# lamloei_node32s3mini_cp2102_main_2layers.net
KiCad netlist of a schematic drawn in EAGLE
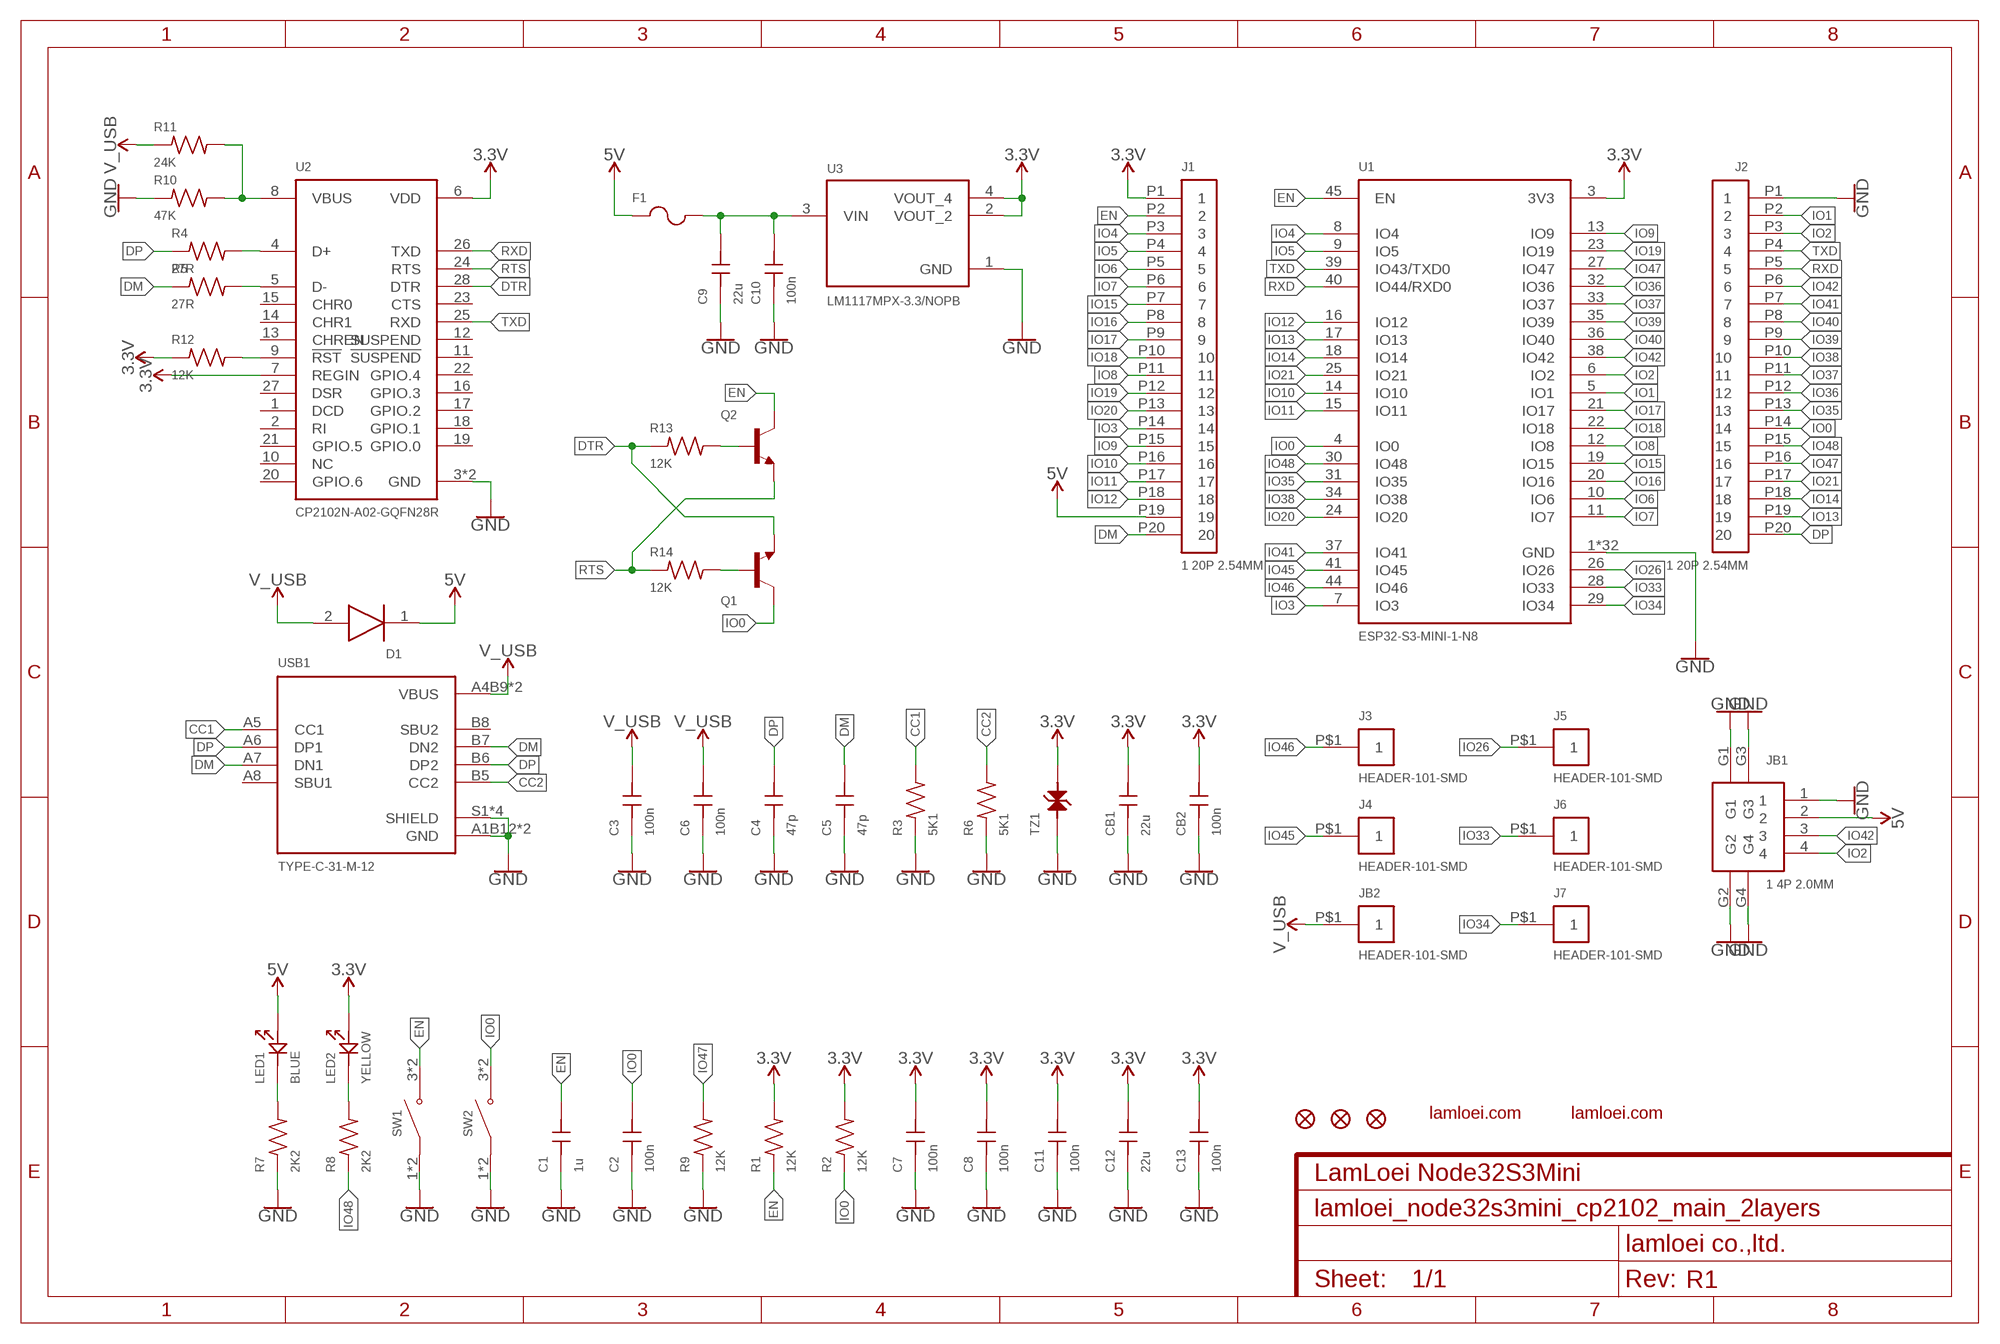
[diagram p0: schematic, sheet 1]

(export (version "E")
  (design (tool "Eeschema 10.0.6"))
  (components
    (comp (ref "C1")
      (value "1u")
      (footprint "eagle-import:GRM155R70J105KA12D")
      (fields (field (name "MANUFACTURER_PART_NUMBER") "GRM155R70J105KA12D"))
      (libsource (lib "eagle-import") (part "GRM155R70J105KA12D"))
    )
    (comp (ref "C2")
      (value "100n")
      (footprint "eagle-import:GCM155R71H104KE02D")
      (fields (field (name "MANUFACTURER_PART_NUMBER") "GCM155R71H104KE02D"))
      (libsource (lib "eagle-import") (part "GCM155R71H104KE02D"))
    )
    (comp (ref "C3")
      (value "100n")
      (footprint "eagle-import:GCM155R71H104KE02D")
      (fields (field (name "MANUFACTURER_PART_NUMBER") "GCM155R71H104KE02D"))
      (libsource (lib "eagle-import") (part "GCM155R71H104KE02D"))
    )
    (comp (ref "C4")
      (value "47p")
      (footprint "eagle-import:GCM1555C1H470JA16D")
      (fields (field (name "MANUFACTURER_PART_NUMBER") "GCM1555C1H470JA16D"))
      (libsource (lib "eagle-import") (part "GCM1555C1H470JA16D"))
    )
    (comp (ref "C5")
      (value "47p")
      (footprint "eagle-import:GCM1555C1H470JA16D")
      (fields (field (name "MANUFACTURER_PART_NUMBER") "GCM1555C1H470JA16D"))
      (libsource (lib "eagle-import") (part "GCM1555C1H470JA16D"))
    )
    (comp (ref "C6")
      (value "100n")
      (footprint "eagle-import:GCM155R71H104KE02D")
      (fields (field (name "MANUFACTURER_PART_NUMBER") "GCM155R71H104KE02D"))
      (libsource (lib "eagle-import") (part "GCM155R71H104KE02D"))
    )
    (comp (ref "C7")
      (value "100n")
      (footprint "eagle-import:GCM155R71H104KE02D")
      (fields (field (name "MANUFACTURER_PART_NUMBER") "GCM155R71H104KE02D"))
      (libsource (lib "eagle-import") (part "GCM155R71H104KE02D"))
    )
    (comp (ref "C8")
      (value "100n")
      (footprint "eagle-import:GCM155R71H104KE02D")
      (fields (field (name "MANUFACTURER_PART_NUMBER") "GCM155R71H104KE02D"))
      (libsource (lib "eagle-import") (part "GCM155R71H104KE02D"))
    )
    (comp (ref "C9")
      (value "22u")
      (footprint "eagle-import:GCM21BR71H105KA03L")
      (fields (field (name "MANUFACTURER_PART_NUMBER") "GCM21BR71H105KA03L"))
      (libsource (lib "eagle-import") (part "GCM21BR71H105KA03L"))
    )
    (comp (ref "C10")
      (value "100n")
      (footprint "eagle-import:GCM155R71H104KE02D")
      (fields (field (name "MANUFACTURER_PART_NUMBER") "GCM155R71H104KE02D"))
      (libsource (lib "eagle-import") (part "GCM155R71H104KE02D"))
    )
    (comp (ref "C11")
      (value "100n")
      (footprint "eagle-import:GCM155R71H104KE02D")
      (fields (field (name "MANUFACTURER_PART_NUMBER") "GCM155R71H104KE02D"))
      (libsource (lib "eagle-import") (part "GCM155R71H104KE02D"))
    )
    (comp (ref "C12")
      (value "22u")
      (footprint "eagle-import:GCM21BR71H105KA03L")
      (fields (field (name "MANUFACTURER_PART_NUMBER") "GCM21BR71H105KA03L"))
      (libsource (lib "eagle-import") (part "GCM21BR71H105KA03L"))
    )
    (comp (ref "C13")
      (value "100n")
      (footprint "eagle-import:GCM155R71H104KE02D")
      (fields (field (name "MANUFACTURER_PART_NUMBER") "GCM155R71H104KE02D"))
      (libsource (lib "eagle-import") (part "GCM155R71H104KE02D"))
    )
    (comp (ref "CB1")
      (value "22u")
      (footprint "eagle-import:GCM21BR71H105KA03L")
      (fields (field (name "MANUFACTURER_PART_NUMBER") "GCM21BR71H105KA03L"))
      (libsource (lib "eagle-import") (part "GCM21BR71H105KA03L"))
    )
    (comp (ref "CB2")
      (value "100n")
      (footprint "eagle-import:GCM155R71H104KE02D")
      (fields (field (name "MANUFACTURER_PART_NUMBER") "GCM155R71H104KE02D"))
      (libsource (lib "eagle-import") (part "GCM155R71H104KE02D"))
    )
    (comp (ref "D1")
      (value "PMEG4050EP,115")
      (footprint "eagle-import:PMEG4050EP,115")
      (fields (field (name "RS_PART_NUMBER") "7805405P"))
      (libsource (lib "eagle-import") (part "PMEG4050EP,115"))
    )
    (comp (ref "F1")
      (value "MF-NSMF050-2")
      (footprint "eagle-import:MF-NSMF050-2")
      (fields (field (name "LCSC_PART") "C75464") (field (name "MANUFACTURER") "BOURNS"))
      (libsource (lib "eagle-import") (part "MF-NSMF050-2"))
    )
    (comp (ref "J1")
      (value "1 20P 2.54MM")
      (footprint "eagle-import:HEADER-120")
      (libsource (lib "eagle-import") (part "HEADER-120"))
    )
    (comp (ref "J2")
      (value "1 20P 2.54MM")
      (footprint "eagle-import:HEADER-120")
      (libsource (lib "eagle-import") (part "lamloei_e77_HEADER-120B_HEADER-120"))
    )
    (comp (ref "J3")
      (value "HEADER-101-SMD")
      (footprint "eagle-import:HEADER-101-SMD")
      (libsource (lib "eagle-import") (part "HEADER-101-SMD"))
    )
    (comp (ref "J4")
      (value "HEADER-101-SMD")
      (footprint "eagle-import:HEADER-101-SMD")
      (libsource (lib "eagle-import") (part "HEADER-101-SMD"))
    )
    (comp (ref "J5")
      (value "HEADER-101-SMD")
      (footprint "eagle-import:HEADER-101-SMD")
      (libsource (lib "eagle-import") (part "HEADER-101-SMD"))
    )
    (comp (ref "J6")
      (value "HEADER-101-SMD")
      (footprint "eagle-import:HEADER-101-SMD")
      (libsource (lib "eagle-import") (part "HEADER-101-SMD"))
    )
    (comp (ref "J7")
      (value "HEADER-101-SMD")
      (footprint "eagle-import:HEADER-101-SMD")
      (libsource (lib "eagle-import") (part "HEADER-101-SMD"))
    )
    (comp (ref "JB1")
      (value "1 4P 2.0MM")
      (footprint "eagle-import:A2012WR-S-4P")
      (libsource (lib "eagle-import") (part "A2012WR-S-4P"))
    )
    (comp (ref "JB2")
      (value "HEADER-101-SMD")
      (footprint "eagle-import:HEADER-101-SMD")
      (libsource (lib "eagle-import") (part "HEADER-101-SMD"))
    )
    (comp (ref "LED1")
      (value "BLUE")
      (footprint "eagle-import:19-217BHC-ZL1M2RY3T")
      (fields (field (name "MANUFACTURER_PART_NUMBER") "19-217BHC-ZL1M2RY3T"))
      (libsource (lib "eagle-import") (part "19-217BHC-ZL1M2RY3T"))
    )
    (comp (ref "LED2")
      (value "YELLOW")
      (footprint "eagle-import:19-213_Y2C-CQ2R2L_3T(CY)")
      (fields (field (name "MANUFACTURER_PART_NUMBER") "19-213/Y2C-CQ2R2L/3T(CY)"))
      (libsource (lib "eagle-import") (part "19-213/Y2C-CQ2R2L/3T(CY)"))
    )
    (comp (ref "Q1")
      (value "BC847B,215")
      (footprint "eagle-import:BC847B,215")
      (fields (field (name "MF") "ON Semiconductor") (field (name "MP") "BC847BLT3G"))
      (libsource (lib "eagle-import") (part "BC847B,215"))
    )
    (comp (ref "Q2")
      (value "BC847B,215")
      (footprint "eagle-import:BC847B,215")
      (fields (field (name "MF") "ON Semiconductor") (field (name "MP") "BC847BLT3G"))
      (libsource (lib "eagle-import") (part "BC847B,215"))
    )
    (comp (ref "R1")
      (value "12K")
      (footprint "eagle-import:R0402")
      (fields
        (field (name "LCSC_PART") "C114760")
        (field (name "MANUFACTURER") "YAGEO")
        (field (name "MANUFACTURER_PART_NUMBER") "RC0402FR-0712KL")
      )
      (libsource (lib "eagle-import") (part "RC0402FR-0712KL"))
    )
    (comp (ref "R2")
      (value "12K")
      (footprint "eagle-import:R0402")
      (fields
        (field (name "LCSC_PART") "C114760")
        (field (name "MANUFACTURER") "YAGEO")
        (field (name "MANUFACTURER_PART_NUMBER") "RC0402FR-0712KL")
      )
      (libsource (lib "eagle-import") (part "RC0402FR-0712KL"))
    )
    (comp (ref "R3")
      (value "5K1")
      (footprint "eagle-import:R0402")
      (fields
        (field (name "LCSC_PART") "C105872")
        (field (name "MANUFACTURER") "YAGEO")
        (field (name "MANUFACTURER_PART_NUMBER") "RC0402FR-075K1L")
      )
      (libsource (lib "eagle-import") (part "RC0402FR-075K1L"))
    )
    (comp (ref "R4")
      (value "27R")
      (footprint "eagle-import:R0402")
      (fields
        (field (name "LCSC_PART") "C138021")
        (field (name "MANUFACTURER") "YAGEO")
        (field (name "MANUFACTURER_PART_NUMBER") "RC0402FR-0727RL")
      )
      (libsource (lib "eagle-import") (part "RC0402FR-0727RL"))
    )
    (comp (ref "R5")
      (value "27R")
      (footprint "eagle-import:R0402")
      (fields
        (field (name "LCSC_PART") "C138021")
        (field (name "MANUFACTURER") "YAGEO")
        (field (name "MANUFACTURER_PART_NUMBER") "RC0402FR-0727RL")
      )
      (libsource (lib "eagle-import") (part "RC0402FR-0727RL"))
    )
    (comp (ref "R6")
      (value "5K1")
      (footprint "eagle-import:R0402")
      (fields
        (field (name "LCSC_PART") "C105872")
        (field (name "MANUFACTURER") "YAGEO")
        (field (name "MANUFACTURER_PART_NUMBER") "RC0402FR-075K1L")
      )
      (libsource (lib "eagle-import") (part "RC0402FR-075K1L"))
    )
    (comp (ref "R7")
      (value "2K2")
      (footprint "eagle-import:R0402")
      (fields
        (field (name "LCSC_PART") "C114762")
        (field (name "MANUFACTURER") "YAGEO")
        (field (name "MANUFACTURER_PART_NUMBER") "RC0402FR-072K2L")
      )
      (libsource (lib "eagle-import") (part "RC0402FR-072K2L"))
    )
    (comp (ref "R8")
      (value "2K2")
      (footprint "eagle-import:R0402")
      (fields
        (field (name "LCSC_PART") "C114762")
        (field (name "MANUFACTURER") "YAGEO")
        (field (name "MANUFACTURER_PART_NUMBER") "RC0402FR-072K2L")
      )
      (libsource (lib "eagle-import") (part "RC0402FR-072K2L"))
    )
    (comp (ref "R9")
      (value "12K")
      (footprint "eagle-import:R0402")
      (fields
        (field (name "LCSC_PART") "C114760")
        (field (name "MANUFACTURER") "YAGEO")
        (field (name "MANUFACTURER_PART_NUMBER") "RC0402FR-0712KL")
      )
      (libsource (lib "eagle-import") (part "RC0402FR-0712KL"))
    )
    (comp (ref "R10")
      (value "47K")
      (footprint "eagle-import:R0402")
      (fields
        (field (name "LCSC_PART") "C93943")
        (field (name "MANUFACTURER") "YAGEO")
        (field (name "MANUFACTURER_PART_NUMBER") "RC0402FR-0747KL")
      )
      (libsource (lib "eagle-import") (part "RC0402FR-0747KL"))
    )
    (comp (ref "R11")
      (value "24K")
      (footprint "eagle-import:R0402")
      (fields
        (field (name "LCSC_PART") "C138026")
        (field (name "MANUFACTURER") "YAGEO")
        (field (name "MANUFACTURER_PART_NUMBER") "RC0402FR-0724KL")
      )
      (libsource (lib "eagle-import") (part "RC0402FR-0724KL"))
    )
    (comp (ref "R12")
      (value "12K")
      (footprint "eagle-import:R0402")
      (fields
        (field (name "LCSC_PART") "C114760")
        (field (name "MANUFACTURER") "YAGEO")
        (field (name "MANUFACTURER_PART_NUMBER") "RC0402FR-0712KL")
      )
      (libsource (lib "eagle-import") (part "RC0402FR-0712KL"))
    )
    (comp (ref "R13")
      (value "12K")
      (footprint "eagle-import:R0402")
      (fields
        (field (name "LCSC_PART") "C114760")
        (field (name "MANUFACTURER") "YAGEO")
        (field (name "MANUFACTURER_PART_NUMBER") "RC0402FR-0712KL")
      )
      (libsource (lib "eagle-import") (part "RC0402FR-0712KL"))
    )
    (comp (ref "R14")
      (value "12K")
      (footprint "eagle-import:R0402")
      (fields
        (field (name "LCSC_PART") "C114760")
        (field (name "MANUFACTURER") "YAGEO")
        (field (name "MANUFACTURER_PART_NUMBER") "RC0402FR-0712KL")
      )
      (libsource (lib "eagle-import") (part "RC0402FR-0712KL"))
    )
    (comp (ref "SW1")
      (value "K2-1808SN-A4SW-01")
      (footprint "eagle-import:K2-1808SN-A4SW-01")
      (fields (field (name "COMMENT") "4-1437565-2") (field (name "MF") "TE Connectivity"))
      (libsource (lib "eagle-import") (part "K2-1808SN-A4SW-01"))
    )
    (comp (ref "SW2")
      (value "K2-1808SN-A4SW-01")
      (footprint "eagle-import:K2-1808SN-A4SW-01")
      (fields (field (name "COMMENT") "4-1437565-2") (field (name "MF") "TE Connectivity"))
      (libsource (lib "eagle-import") (part "K2-1808SN-A4SW-01"))
    )
    (comp (ref "TZ1")
      (value "LXES15AAA1-153")
      (footprint "eagle-import:LXES15AAA1-153")
      (fields (field (name "LCSC_PART") "C86141") (field (name "MANUFACTURER") "Murata"))
      (libsource (lib "eagle-import") (part "LXES15AAA1-153"))
    )
    (comp (ref "U1")
      (value "ESP32-S3-MINI-1-N8")
      (footprint "eagle-import:ESP32-S3-MINI-1-N8")
      (libsource (lib "eagle-import") (part "ESP32-S3-MINI-1-N8"))
    )
    (comp (ref "U2")
      (value "CP2102N-A02-GQFN28R")
      (footprint "eagle-import:CP2102N-A02-GQFN28R")
      (libsource (lib "eagle-import") (part "CP2102N-A02-GQFN28R"))
    )
    (comp (ref "U3")
      (value "LM1117MPX-3.3/NOPB")
      (footprint "eagle-import:LM1117MPX-3.3_NOPB")
      (fields (field (name "MF") "Texas Instruments"))
      (libsource (lib "eagle-import") (part "LM1117MPX-3.3/NOPB"))
    )
    (comp (ref "USB1")
      (value "TYPE-C-31-M-12")
      (footprint "eagle-import:TYPE-C-31-M-12")
      (fields (field (name "MF") "HRO Electronics Co., Ltd."))
      (libsource (lib "eagle-import") (part "TYPE-C-31-M-12"))
    )
    (comp (ref "ZFD1")
      (value "FIDUCIAL1X2")
      (footprint "eagle-import:FIDUCIAL-1X2")
      (libsource (lib "eagle-import") (part "FIDUCIAL1X2"))
    )
    (comp (ref "ZFD2")
      (value "FIDUCIAL1X2")
      (footprint "eagle-import:FIDUCIAL-1X2")
      (libsource (lib "eagle-import") (part "FIDUCIAL1X2"))
    )
    (comp (ref "ZFD3")
      (value "FIDUCIAL1X2")
      (footprint "eagle-import:FIDUCIAL-1X2")
      (libsource (lib "eagle-import") (part "FIDUCIAL1X2"))
    )
    (comp (ref "ZL1")
      (value "LAMLEOI_LOGO_3")
      (footprint "eagle-import:LAMLEOI_LOGO_3")
      (libsource (lib "eagle-import") (part "LAMLEOI_LOGO_3"))
    )
    (comp (ref "ZL2")
      (value "LAMLEOI_LOGO_3")
      (footprint "eagle-import:LAMLEOI_LOGO_3")
      (libsource (lib "eagle-import") (part "LAMLEOI_LOGO_3"))
    )
  )
  (nets
    (net (code "1") (name "/GPIO.5") (class "Default")
      (node (ref "U2") (pin "21") (pinfunction "GPIO.5_21") (pintype "power_in"))
    )
    (net (code "2") (name "3.3V") (class "Default")
      (node (ref "C11") (pin "2") (pinfunction "2_2") (pintype "passive"))
      (node (ref "C12") (pin "2") (pinfunction "2_2") (pintype "passive"))
      (node (ref "C13") (pin "2") (pinfunction "2_2") (pintype "passive"))
      (node (ref "C7") (pin "2") (pinfunction "2_2") (pintype "passive"))
      (node (ref "C8") (pin "2") (pinfunction "2_2") (pintype "passive"))
      (node (ref "CB1") (pin "2") (pinfunction "2_2") (pintype "passive"))
      (node (ref "CB2") (pin "2") (pinfunction "2_2") (pintype "passive"))
      (node (ref "J1") (pin "P1") (pinfunction "1_P1") (pintype "passive"))
      (node (ref "LED2") (pin "2") (pinfunction "2_2") (pintype "passive"))
      (node (ref "R1") (pin "2") (pinfunction "2_2") (pintype "passive"))
      (node (ref "R12") (pin "1") (pinfunction "1_1") (pintype "passive"))
      (node (ref "R2") (pin "2") (pinfunction "2_2") (pintype "passive"))
      (node (ref "TZ1") (pin "2") (pinfunction "2_2") (pintype "passive"))
      (node (ref "U1") (pin "3") (pinfunction "3V3_3") (pintype "power_in"))
      (node (ref "U2") (pin "6") (pinfunction "VDD_6") (pintype "power_in"))
      (node (ref "U2") (pin "7") (pinfunction "REGIN_7") (pintype "input"))
      (node (ref "U3") (pin "2") (pinfunction "VOUT_2_2") (pintype "output"))
      (node (ref "U3") (pin "4") (pinfunction "VOUT_4_4") (pintype "output"))
    )
    (net (code "3") (name "5V") (class "Default")
      (node (ref "D1") (pin "1") (pinfunction "K_1") (pintype "bidirectional"))
      (node (ref "F1") (pin "1") (pinfunction "1_1") (pintype "passive"))
      (node (ref "J1") (pin "P19") (pinfunction "19_P19") (pintype "passive"))
      (node (ref "JB1") (pin "2") (pinfunction "2_2") (pintype "bidirectional"))
      (node (ref "LED1") (pin "2") (pinfunction "2_2") (pintype "passive"))
    )
    (net (code "4") (name "CC1") (class "Default")
      (node (ref "R3") (pin "2") (pinfunction "2_2") (pintype "passive"))
      (node (ref "USB1") (pin "A5") (pinfunction "CC1_A5") (pintype "bidirectional"))
    )
    (net (code "5") (name "CC2") (class "Default")
      (node (ref "R6") (pin "2") (pinfunction "2_2") (pintype "passive"))
      (node (ref "USB1") (pin "B5") (pinfunction "CC2_B5") (pintype "bidirectional"))
    )
    (net (code "6") (name "DM") (class "Default")
      (node (ref "C5") (pin "2") (pinfunction "2_2") (pintype "passive"))
      (node (ref "J1") (pin "P20") (pinfunction "20_P20") (pintype "passive"))
      (node (ref "R5") (pin "1") (pinfunction "1_1") (pintype "passive"))
      (node (ref "USB1") (pin "A7") (pinfunction "DN1_A7") (pintype "bidirectional"))
      (node (ref "USB1") (pin "B7") (pinfunction "DN2_B7") (pintype "bidirectional"))
    )
    (net (code "7") (name "DP") (class "Default")
      (node (ref "C4") (pin "2") (pinfunction "2_2") (pintype "passive"))
      (node (ref "J2") (pin "P20") (pinfunction "20_P20") (pintype "passive"))
      (node (ref "R4") (pin "1") (pinfunction "1_1") (pintype "passive"))
      (node (ref "USB1") (pin "A6") (pinfunction "DP1_A6") (pintype "bidirectional"))
      (node (ref "USB1") (pin "B6") (pinfunction "DP2_B6") (pintype "bidirectional"))
    )
    (net (code "8") (name "DTR") (class "Default")
      (node (ref "Q1") (pin "E") (pinfunction "E_E") (pintype "passive"))
      (node (ref "R13") (pin "1") (pinfunction "1_1") (pintype "passive"))
      (node (ref "U2") (pin "28") (pinfunction "DTR_28") (pintype "output"))
    )
    (net (code "9") (name "EN") (class "Default")
      (node (ref "C1") (pin "2") (pinfunction "2_2") (pintype "passive"))
      (node (ref "J1") (pin "P2") (pinfunction "2_P2") (pintype "passive"))
      (node (ref "Q2") (pin "C") (pinfunction "C_C") (pintype "passive"))
      (node (ref "R1") (pin "1") (pinfunction "1_1") (pintype "passive"))
      (node (ref "SW1") (pin "3") (pinfunction "NO_3") (pintype "passive"))
      (node (ref "SW1") (pin "4") (pinfunction "NO_4") (pintype "passive"))
      (node (ref "U1") (pin "45") (pinfunction "EN_45") (pintype "input"))
    )
    (net (code "10") (name "GND") (class "Default")
      (node (ref "C1") (pin "1") (pinfunction "1_1") (pintype "passive"))
      (node (ref "C10") (pin "1") (pinfunction "1_1") (pintype "passive"))
      (node (ref "C11") (pin "1") (pinfunction "1_1") (pintype "passive"))
      (node (ref "C12") (pin "1") (pinfunction "1_1") (pintype "passive"))
      (node (ref "C13") (pin "1") (pinfunction "1_1") (pintype "passive"))
      (node (ref "C2") (pin "1") (pinfunction "1_1") (pintype "passive"))
      (node (ref "C3") (pin "1") (pinfunction "1_1") (pintype "passive"))
      (node (ref "C4") (pin "1") (pinfunction "1_1") (pintype "passive"))
      (node (ref "C5") (pin "1") (pinfunction "1_1") (pintype "passive"))
      (node (ref "C6") (pin "1") (pinfunction "1_1") (pintype "passive"))
      (node (ref "C7") (pin "1") (pinfunction "1_1") (pintype "passive"))
      (node (ref "C8") (pin "1") (pinfunction "1_1") (pintype "passive"))
      (node (ref "C9") (pin "1") (pinfunction "1_1") (pintype "passive"))
      (node (ref "CB1") (pin "1") (pinfunction "1_1") (pintype "passive"))
      (node (ref "CB2") (pin "1") (pinfunction "1_1") (pintype "passive"))
      (node (ref "J2") (pin "P1") (pinfunction "1_P1") (pintype "passive"))
      (node (ref "JB1") (pin "1") (pinfunction "1_1") (pintype "bidirectional"))
      (node (ref "JB1") (pin "G1") (pinfunction "G1_G1") (pintype "bidirectional"))
      (node (ref "JB1") (pin "G2") (pinfunction "G2_G2") (pintype "bidirectional"))
      (node (ref "JB1") (pin "G3") (pinfunction "G3_G3") (pintype "bidirectional"))
      (node (ref "JB1") (pin "G4") (pinfunction "G4_G4") (pintype "bidirectional"))
      (node (ref "R10") (pin "1") (pinfunction "1_1") (pintype "passive"))
      (node (ref "R3") (pin "1") (pinfunction "1_1") (pintype "passive"))
      (node (ref "R6") (pin "1") (pinfunction "1_1") (pintype "passive"))
      (node (ref "R7") (pin "1") (pinfunction "1_1") (pintype "passive"))
      (node (ref "R9") (pin "1") (pinfunction "1_1") (pintype "passive"))
      (node (ref "SW1") (pin "1") (pinfunction "COM_1") (pintype "passive"))
      (node (ref "SW1") (pin "2") (pinfunction "COM_2") (pintype "passive"))
      (node (ref "SW2") (pin "1") (pinfunction "COM_1") (pintype "passive"))
      (node (ref "SW2") (pin "2") (pinfunction "COM_2") (pintype "passive"))
      (node (ref "TZ1") (pin "1") (pinfunction "1_1") (pintype "passive"))
      (node (ref "U1") (pin "1") (pinfunction "GND_1") (pintype "power_in"))
      (node (ref "U1") (pin "2") (pinfunction "GND_2") (pintype "power_in"))
      (node (ref "U1") (pin "42") (pinfunction "GND_42") (pintype "power_in"))
      (node (ref "U1") (pin "43") (pinfunction "GND_43") (pintype "power_in"))
      (node (ref "U1") (pin "46") (pinfunction "GND_46") (pintype "power_in"))
      (node (ref "U1") (pin "47") (pinfunction "GND_47") (pintype "power_in"))
      (node (ref "U1") (pin "48") (pinfunction "GND_48") (pintype "power_in"))
      (node (ref "U1") (pin "49") (pinfunction "GND_49") (pintype "power_in"))
      (node (ref "U1") (pin "50") (pinfunction "GND_50") (pintype "power_in"))
      (node (ref "U1") (pin "51") (pinfunction "GND_51") (pintype "power_in"))
      (node (ref "U1") (pin "52") (pinfunction "GND_52") (pintype "power_in"))
      (node (ref "U1") (pin "53") (pinfunction "GND_53") (pintype "power_in"))
      (node (ref "U1") (pin "54") (pinfunction "GND_54") (pintype "power_in"))
      (node (ref "U1") (pin "55") (pinfunction "GND_55") (pintype "power_in"))
      (node (ref "U1") (pin "56") (pinfunction "GND_56") (pintype "power_in"))
      (node (ref "U1") (pin "57") (pinfunction "GND_57") (pintype "power_in"))
      (node (ref "U1") (pin "58") (pinfunction "GND_58") (pintype "power_in"))
      (node (ref "U1") (pin "59") (pinfunction "GND_59") (pintype "power_in"))
      (node (ref "U1") (pin "60") (pinfunction "GND_60") (pintype "power_in"))
      (node (ref "U1") (pin "61") (pinfunction "GND_61") (pintype "power_in"))
      (node (ref "U1") (pin "61_1") (pinfunction "GND_61_1") (pintype "power_in"))
      (node (ref "U1") (pin "61_2") (pinfunction "GND_61_2") (pintype "power_in"))
      (node (ref "U1") (pin "61_3") (pinfunction "GND_61_3") (pintype "power_in"))
      (node (ref "U1") (pin "61_4") (pinfunction "GND_61_4") (pintype "power_in"))
      (node (ref "U1") (pin "61_5") (pinfunction "GND_61_5") (pintype "power_in"))
      (node (ref "U1") (pin "61_6") (pinfunction "GND_61_6") (pintype "power_in"))
      (node (ref "U1") (pin "61_7") (pinfunction "GND_61_7") (pintype "power_in"))
      (node (ref "U1") (pin "61_8") (pinfunction "GND_61_8") (pintype "power_in"))
      (node (ref "U1") (pin "62") (pinfunction "GND_62") (pintype "power_in"))
      (node (ref "U1") (pin "63") (pinfunction "GND_63") (pintype "power_in"))
      (node (ref "U1") (pin "64") (pinfunction "GND_64") (pintype "power_in"))
      (node (ref "U1") (pin "65") (pinfunction "GND_65") (pintype "power_in"))
      (node (ref "U2") (pin "29") (pinfunction "GND_29") (pintype "power_in"))
      (node (ref "U2") (pin "3") (pinfunction "GND_3") (pintype "power_in"))
      (node (ref "U3") (pin "1") (pinfunction "GND_1") (pintype "power_in"))
      (node (ref "USB1") (pin "A1B12") (pinfunction "GND_A1B12") (pintype "power_in"))
      (node (ref "USB1") (pin "B1A12") (pinfunction "GND_B1A12") (pintype "power_in"))
      (node (ref "USB1") (pin "S1") (pinfunction "SHIELD_S1") (pintype "passive"))
      (node (ref "USB1") (pin "S2") (pinfunction "SHIELD_S2") (pintype "passive"))
      (node (ref "USB1") (pin "S3") (pinfunction "SHIELD_S3") (pintype "passive"))
      (node (ref "USB1") (pin "S4") (pinfunction "SHIELD_S4") (pintype "passive"))
    )
    (net (code "11") (name "IO0") (class "Default")
      (node (ref "C2") (pin "2") (pinfunction "2_2") (pintype "passive"))
      (node (ref "J2") (pin "P14") (pinfunction "14_P14") (pintype "passive"))
      (node (ref "Q1") (pin "C") (pinfunction "C_C") (pintype "passive"))
      (node (ref "R2") (pin "1") (pinfunction "1_1") (pintype "passive"))
      (node (ref "SW2") (pin "3") (pinfunction "NO_3") (pintype "passive"))
      (node (ref "SW2") (pin "4") (pinfunction "NO_4") (pintype "passive"))
      (node (ref "U1") (pin "4") (pinfunction "IO0_4") (pintype "bidirectional"))
    )
    (net (code "12") (name "IO1") (class "Default")
      (node (ref "J2") (pin "P2") (pinfunction "2_P2") (pintype "passive"))
      (node (ref "U1") (pin "5") (pinfunction "IO1_5") (pintype "bidirectional"))
    )
    (net (code "13") (name "IO2") (class "Default")
      (node (ref "J2") (pin "P3") (pinfunction "3_P3") (pintype "passive"))
      (node (ref "JB1") (pin "4") (pinfunction "4_4") (pintype "bidirectional"))
      (node (ref "U1") (pin "6") (pinfunction "IO2_6") (pintype "bidirectional"))
    )
    (net (code "14") (name "IO3") (class "Default")
      (node (ref "J1") (pin "P14") (pinfunction "14_P14") (pintype "passive"))
      (node (ref "U1") (pin "7") (pinfunction "IO3_7") (pintype "bidirectional"))
    )
    (net (code "15") (name "IO4") (class "Default")
      (node (ref "J1") (pin "P3") (pinfunction "3_P3") (pintype "passive"))
      (node (ref "U1") (pin "8") (pinfunction "IO4_8") (pintype "input"))
    )
    (net (code "16") (name "IO5") (class "Default")
      (node (ref "J1") (pin "P4") (pinfunction "4_P4") (pintype "passive"))
      (node (ref "U1") (pin "9") (pinfunction "IO5_9") (pintype "input"))
    )
    (net (code "17") (name "IO6") (class "Default")
      (node (ref "J1") (pin "P5") (pinfunction "5_P5") (pintype "passive"))
      (node (ref "U1") (pin "10") (pinfunction "IO6_10") (pintype "bidirectional"))
    )
    (net (code "18") (name "IO7") (class "Default")
      (node (ref "J1") (pin "P6") (pinfunction "6_P6") (pintype "passive"))
      (node (ref "U1") (pin "11") (pinfunction "IO7_11") (pintype "bidirectional"))
    )
    (net (code "19") (name "IO8") (class "Default")
      (node (ref "J1") (pin "P11") (pinfunction "11_P11") (pintype "passive"))
      (node (ref "U1") (pin "12") (pinfunction "IO8_12") (pintype "bidirectional"))
    )
    (net (code "20") (name "IO9") (class "Default")
      (node (ref "J1") (pin "P15") (pinfunction "15_P15") (pintype "passive"))
      (node (ref "U1") (pin "13") (pinfunction "IO9_13") (pintype "bidirectional"))
    )
    (net (code "21") (name "IO10") (class "Default")
      (node (ref "J1") (pin "P16") (pinfunction "16_P16") (pintype "passive"))
      (node (ref "U1") (pin "14") (pinfunction "IO10_14") (pintype "bidirectional"))
    )
    (net (code "22") (name "IO11") (class "Default")
      (node (ref "J1") (pin "P17") (pinfunction "17_P17") (pintype "passive"))
      (node (ref "U1") (pin "15") (pinfunction "IO11_15") (pintype "bidirectional"))
    )
    (net (code "23") (name "IO12") (class "Default")
      (node (ref "J1") (pin "P18") (pinfunction "18_P18") (pintype "passive"))
      (node (ref "U1") (pin "16") (pinfunction "IO12_16") (pintype "bidirectional"))
    )
    (net (code "24") (name "IO13") (class "Default")
      (node (ref "J2") (pin "P19") (pinfunction "19_P19") (pintype "passive"))
      (node (ref "U1") (pin "17") (pinfunction "IO13_17") (pintype "bidirectional"))
    )
    (net (code "25") (name "IO14") (class "Default")
      (node (ref "J2") (pin "P18") (pinfunction "18_P18") (pintype "passive"))
      (node (ref "U1") (pin "18") (pinfunction "IO14_18") (pintype "bidirectional"))
    )
    (net (code "26") (name "IO15") (class "Default")
      (node (ref "J1") (pin "P7") (pinfunction "7_P7") (pintype "passive"))
      (node (ref "U1") (pin "19") (pinfunction "IO15_19") (pintype "bidirectional"))
    )
    (net (code "27") (name "IO16") (class "Default")
      (node (ref "J1") (pin "P8") (pinfunction "8_P8") (pintype "passive"))
      (node (ref "U1") (pin "20") (pinfunction "IO16_20") (pintype "bidirectional"))
    )
    (net (code "28") (name "IO17") (class "Default")
      (node (ref "J1") (pin "P9") (pinfunction "9_P9") (pintype "passive"))
      (node (ref "U1") (pin "21") (pinfunction "IO17_21") (pintype "bidirectional"))
    )
    (net (code "29") (name "IO18") (class "Default")
      (node (ref "J1") (pin "P10") (pinfunction "10_P10") (pintype "passive"))
      (node (ref "U1") (pin "22") (pinfunction "IO18_22") (pintype "bidirectional"))
    )
    (net (code "30") (name "IO19") (class "Default")
      (node (ref "J1") (pin "P12") (pinfunction "12_P12") (pintype "passive"))
      (node (ref "U1") (pin "23") (pinfunction "IO19_23") (pintype "bidirectional"))
    )
    (net (code "31") (name "IO20") (class "Default")
      (node (ref "J1") (pin "P13") (pinfunction "13_P13") (pintype "passive"))
      (node (ref "U1") (pin "24") (pinfunction "IO20_24") (pintype "bidirectional"))
    )
    (net (code "32") (name "IO21") (class "Default")
      (node (ref "J2") (pin "P17") (pinfunction "17_P17") (pintype "passive"))
      (node (ref "U1") (pin "25") (pinfunction "IO21_25") (pintype "bidirectional"))
    )
    (net (code "33") (name "IO26") (class "Default")
      (node (ref "J5") (pin "P$1") (pinfunction "1_P$1") (pintype "passive"))
      (node (ref "U1") (pin "26") (pinfunction "IO26_26") (pintype "bidirectional"))
    )
    (net (code "34") (name "IO33") (class "Default")
      (node (ref "J6") (pin "P$1") (pinfunction "1_P$1") (pintype "passive"))
      (node (ref "U1") (pin "28") (pinfunction "IO33_28") (pintype "bidirectional"))
    )
    (net (code "35") (name "IO34") (class "Default")
      (node (ref "J7") (pin "P$1") (pinfunction "1_P$1") (pintype "passive"))
      (node (ref "U1") (pin "29") (pinfunction "IO34_29") (pintype "bidirectional"))
    )
    (net (code "36") (name "IO35") (class "Default")
      (node (ref "J2") (pin "P13") (pinfunction "13_P13") (pintype "passive"))
      (node (ref "U1") (pin "31") (pinfunction "IO35_31") (pintype "bidirectional"))
    )
    (net (code "37") (name "IO36") (class "Default")
      (node (ref "J2") (pin "P12") (pinfunction "12_P12") (pintype "passive"))
      (node (ref "U1") (pin "32") (pinfunction "IO36_32") (pintype "bidirectional"))
    )
    (net (code "38") (name "IO37") (class "Default")
      (node (ref "J2") (pin "P11") (pinfunction "11_P11") (pintype "passive"))
      (node (ref "U1") (pin "33") (pinfunction "IO37_33") (pintype "bidirectional"))
    )
    (net (code "39") (name "IO38") (class "Default")
      (node (ref "J2") (pin "P10") (pinfunction "10_P10") (pintype "passive"))
      (node (ref "U1") (pin "34") (pinfunction "IO38_34") (pintype "bidirectional"))
    )
    (net (code "40") (name "IO39") (class "Default")
      (node (ref "J2") (pin "P9") (pinfunction "9_P9") (pintype "passive"))
      (node (ref "U1") (pin "35") (pinfunction "IO39_35") (pintype "bidirectional"))
    )
    (net (code "41") (name "IO40") (class "Default")
      (node (ref "J2") (pin "P8") (pinfunction "8_P8") (pintype "passive"))
      (node (ref "U1") (pin "36") (pinfunction "IO40_36") (pintype "bidirectional"))
    )
    (net (code "42") (name "IO41") (class "Default")
      (node (ref "J2") (pin "P7") (pinfunction "7_P7") (pintype "passive"))
      (node (ref "U1") (pin "37") (pinfunction "IO41_37") (pintype "bidirectional"))
    )
    (net (code "43") (name "IO42") (class "Default")
      (node (ref "J2") (pin "P6") (pinfunction "6_P6") (pintype "passive"))
      (node (ref "JB1") (pin "3") (pinfunction "3_3") (pintype "bidirectional"))
      (node (ref "U1") (pin "38") (pinfunction "IO42_38") (pintype "bidirectional"))
    )
    (net (code "44") (name "IO45") (class "Default")
      (node (ref "J4") (pin "P$1") (pinfunction "1_P$1") (pintype "passive"))
      (node (ref "U1") (pin "41") (pinfunction "IO45_41") (pintype "bidirectional"))
    )
    (net (code "45") (name "IO46") (class "Default")
      (node (ref "J3") (pin "P$1") (pinfunction "1_P$1") (pintype "passive"))
      (node (ref "U1") (pin "44") (pinfunction "IO46_44") (pintype "bidirectional"))
    )
    (net (code "46") (name "IO47") (class "Default")
      (node (ref "J2") (pin "P16") (pinfunction "16_P16") (pintype "passive"))
      (node (ref "R9") (pin "2") (pinfunction "2_2") (pintype "passive"))
      (node (ref "U1") (pin "27") (pinfunction "IO47_27") (pintype "bidirectional"))
    )
    (net (code "47") (name "IO48") (class "Default")
      (node (ref "J2") (pin "P15") (pinfunction "15_P15") (pintype "passive"))
      (node (ref "R8") (pin "1") (pinfunction "1_1") (pintype "passive"))
      (node (ref "U1") (pin "30") (pinfunction "IO48_30") (pintype "bidirectional"))
    )
    (net (code "48") (name "Net-(LED1-Pad1)") (class "Default")
      (node (ref "LED1") (pin "1") (pinfunction "1_1") (pintype "passive"))
      (node (ref "R7") (pin "2") (pinfunction "2_2") (pintype "passive"))
    )
    (net (code "49") (name "Net-(LED2-Pad1)") (class "Default")
      (node (ref "LED2") (pin "1") (pinfunction "1_1") (pintype "passive"))
      (node (ref "R8") (pin "2") (pinfunction "2_2") (pintype "passive"))
    )
    (net (code "50") (name "Net-(Q1-PadB)") (class "Default")
      (node (ref "Q1") (pin "B") (pinfunction "B_B") (pintype "passive"))
      (node (ref "R14") (pin "2") (pinfunction "2_2") (pintype "passive"))
    )
    (net (code "51") (name "Net-(Q2-PadB)") (class "Default")
      (node (ref "Q2") (pin "B") (pinfunction "B_B") (pintype "passive"))
      (node (ref "R13") (pin "2") (pinfunction "2_2") (pintype "passive"))
    )
    (net (code "52") (name "Net-(U2-D+)") (class "Default")
      (node (ref "R4") (pin "2") (pinfunction "2_2") (pintype "passive"))
      (node (ref "U2") (pin "4") (pinfunction "D+_4") (pintype "bidirectional"))
    )
    (net (code "53") (name "Net-(U2-D-)") (class "Default")
      (node (ref "R5") (pin "2") (pinfunction "2_2") (pintype "passive"))
      (node (ref "U2") (pin "5") (pinfunction "D-_5") (pintype "bidirectional"))
    )
    (net (code "54") (name "Net-(U2-VBUS)") (class "Default")
      (node (ref "R10") (pin "2") (pinfunction "2_2") (pintype "passive"))
      (node (ref "R11") (pin "2") (pinfunction "2_2") (pintype "passive"))
      (node (ref "U2") (pin "8") (pinfunction "VBUS_8") (pintype "input"))
    )
    (net (code "55") (name "Net-(U2-~{RST})") (class "Default")
      (node (ref "R12") (pin "2") (pinfunction "2_2") (pintype "passive"))
      (node (ref "U2") (pin "9") (pinfunction "~{RST}_9") (pintype "input"))
    )
    (net (code "56") (name "Net-(U3-VIN)") (class "Default")
      (node (ref "C10") (pin "2") (pinfunction "2_2") (pintype "passive"))
      (node (ref "C9") (pin "2") (pinfunction "2_2") (pintype "passive"))
      (node (ref "F1") (pin "2") (pinfunction "2_2") (pintype "passive"))
      (node (ref "U3") (pin "3") (pinfunction "VIN_3") (pintype "input"))
    )
    (net (code "57") (name "RTS") (class "Default")
      (node (ref "Q2") (pin "E") (pinfunction "E_E") (pintype "passive"))
      (node (ref "R14") (pin "1") (pinfunction "1_1") (pintype "passive"))
      (node (ref "U2") (pin "24") (pinfunction "RTS_24") (pintype "output"))
    )
    (net (code "58") (name "RXD") (class "Default")
      (node (ref "J2") (pin "P5") (pinfunction "5_P5") (pintype "passive"))
      (node (ref "U1") (pin "40") (pinfunction "IO44/RXD0_40") (pintype "bidirectional"))
      (node (ref "U2") (pin "26") (pinfunction "TXD_26") (pintype "output"))
    )
    (net (code "59") (name "TXD") (class "Default")
      (node (ref "J2") (pin "P4") (pinfunction "4_P4") (pintype "passive"))
      (node (ref "U1") (pin "39") (pinfunction "IO43/TXD0_39") (pintype "bidirectional"))
      (node (ref "U2") (pin "25") (pinfunction "RXD_25") (pintype "input"))
    )
    (net (code "60") (name "V_USB") (class "Default")
      (node (ref "C3") (pin "2") (pinfunction "2_2") (pintype "passive"))
      (node (ref "C6") (pin "2") (pinfunction "2_2") (pintype "passive"))
      (node (ref "D1") (pin "2") (pinfunction "A_2") (pintype "bidirectional"))
      (node (ref "JB2") (pin "P$1") (pinfunction "1_P$1") (pintype "passive"))
      (node (ref "R11") (pin "1") (pinfunction "1_1") (pintype "passive"))
      (node (ref "USB1") (pin "A4B9") (pinfunction "VBUS_A4B9") (pintype "power_in"))
      (node (ref "USB1") (pin "B4A9") (pinfunction "VBUS_B4A9") (pintype "power_in"))
    )
    (net (code "61") (name "unconnected-(U2-CHR0-Pad15)") (class "Default")
      (node (ref "U2") (pin "15") (pinfunction "CHR0_15") (pintype "input"))
    )
    (net (code "62") (name "unconnected-(U2-CHR1-Pad14)") (class "Default")
      (node (ref "U2") (pin "14") (pinfunction "CHR1_14") (pintype "input"))
    )
    (net (code "63") (name "unconnected-(U2-CHREN-Pad13)") (class "Default")
      (node (ref "U2") (pin "13") (pinfunction "CHREN_13") (pintype "input"))
    )
    (net (code "64") (name "unconnected-(U2-CTS-Pad23)") (class "Default")
      (node (ref "U2") (pin "23") (pinfunction "CTS_23") (pintype "input"))
    )
    (net (code "65") (name "unconnected-(U2-DCD-Pad1)") (class "Default")
      (node (ref "U2") (pin "1") (pinfunction "DCD_1") (pintype "input"))
    )
    (net (code "66") (name "unconnected-(U2-DSR-Pad27)") (class "Default")
      (node (ref "U2") (pin "27") (pinfunction "DSR_27") (pintype "input"))
    )
    (net (code "67") (name "unconnected-(U2-GPIO.0-Pad19)") (class "Default")
      (node (ref "U2") (pin "19") (pinfunction "GPIO.0_19") (pintype "bidirectional"))
    )
    (net (code "68") (name "unconnected-(U2-GPIO.1-Pad18)") (class "Default")
      (node (ref "U2") (pin "18") (pinfunction "GPIO.1_18") (pintype "bidirectional"))
    )
    (net (code "69") (name "unconnected-(U2-GPIO.2-Pad17)") (class "Default")
      (node (ref "U2") (pin "17") (pinfunction "GPIO.2_17") (pintype "bidirectional"))
    )
    (net (code "70") (name "unconnected-(U2-GPIO.3-Pad16)") (class "Default")
      (node (ref "U2") (pin "16") (pinfunction "GPIO.3_16") (pintype "bidirectional"))
    )
    (net (code "71") (name "unconnected-(U2-GPIO.4-Pad22)") (class "Default")
      (node (ref "U2") (pin "22") (pinfunction "GPIO.4_22") (pintype "bidirectional"))
    )
    (net (code "72") (name "unconnected-(U2-GPIO.6-Pad20)") (class "Default")
      (node (ref "U2") (pin "20") (pinfunction "GPIO.6_20") (pintype "passive"))
    )
    (net (code "73") (name "unconnected-(U2-NC-Pad10)") (class "Default")
      (node (ref "U2") (pin "10") (pinfunction "NC_10") (pintype "bidirectional"))
    )
    (net (code "74") (name "unconnected-(U2-RI-Pad2)") (class "Default")
      (node (ref "U2") (pin "2") (pinfunction "RI_2") (pintype "input"))
    )
    (net (code "75") (name "unconnected-(U2-SUSPEND-Pad12)") (class "Default")
      (node (ref "U2") (pin "12") (pinfunction "SUSPEND_12") (pintype "output"))
    )
    (net (code "76") (name "unconnected-(U2-~{SUSPEND}-Pad11)") (class "Default")
      (node (ref "U2") (pin "11") (pinfunction "~{SUSPEND}_11") (pintype "output"))
    )
    (net (code "77") (name "unconnected-(USB1-SBU1-PadA8)") (class "Default")
      (node (ref "USB1") (pin "A8") (pinfunction "SBU1_A8") (pintype "bidirectional"))
    )
    (net (code "78") (name "unconnected-(USB1-SBU2-PadB8)") (class "Default")
      (node (ref "USB1") (pin "B8") (pinfunction "SBU2_B8") (pintype "bidirectional"))
    )
  )
)
